# Nikon_PowerBoardV3.net
KiCad netlist of a schematic drawn in EAGLE
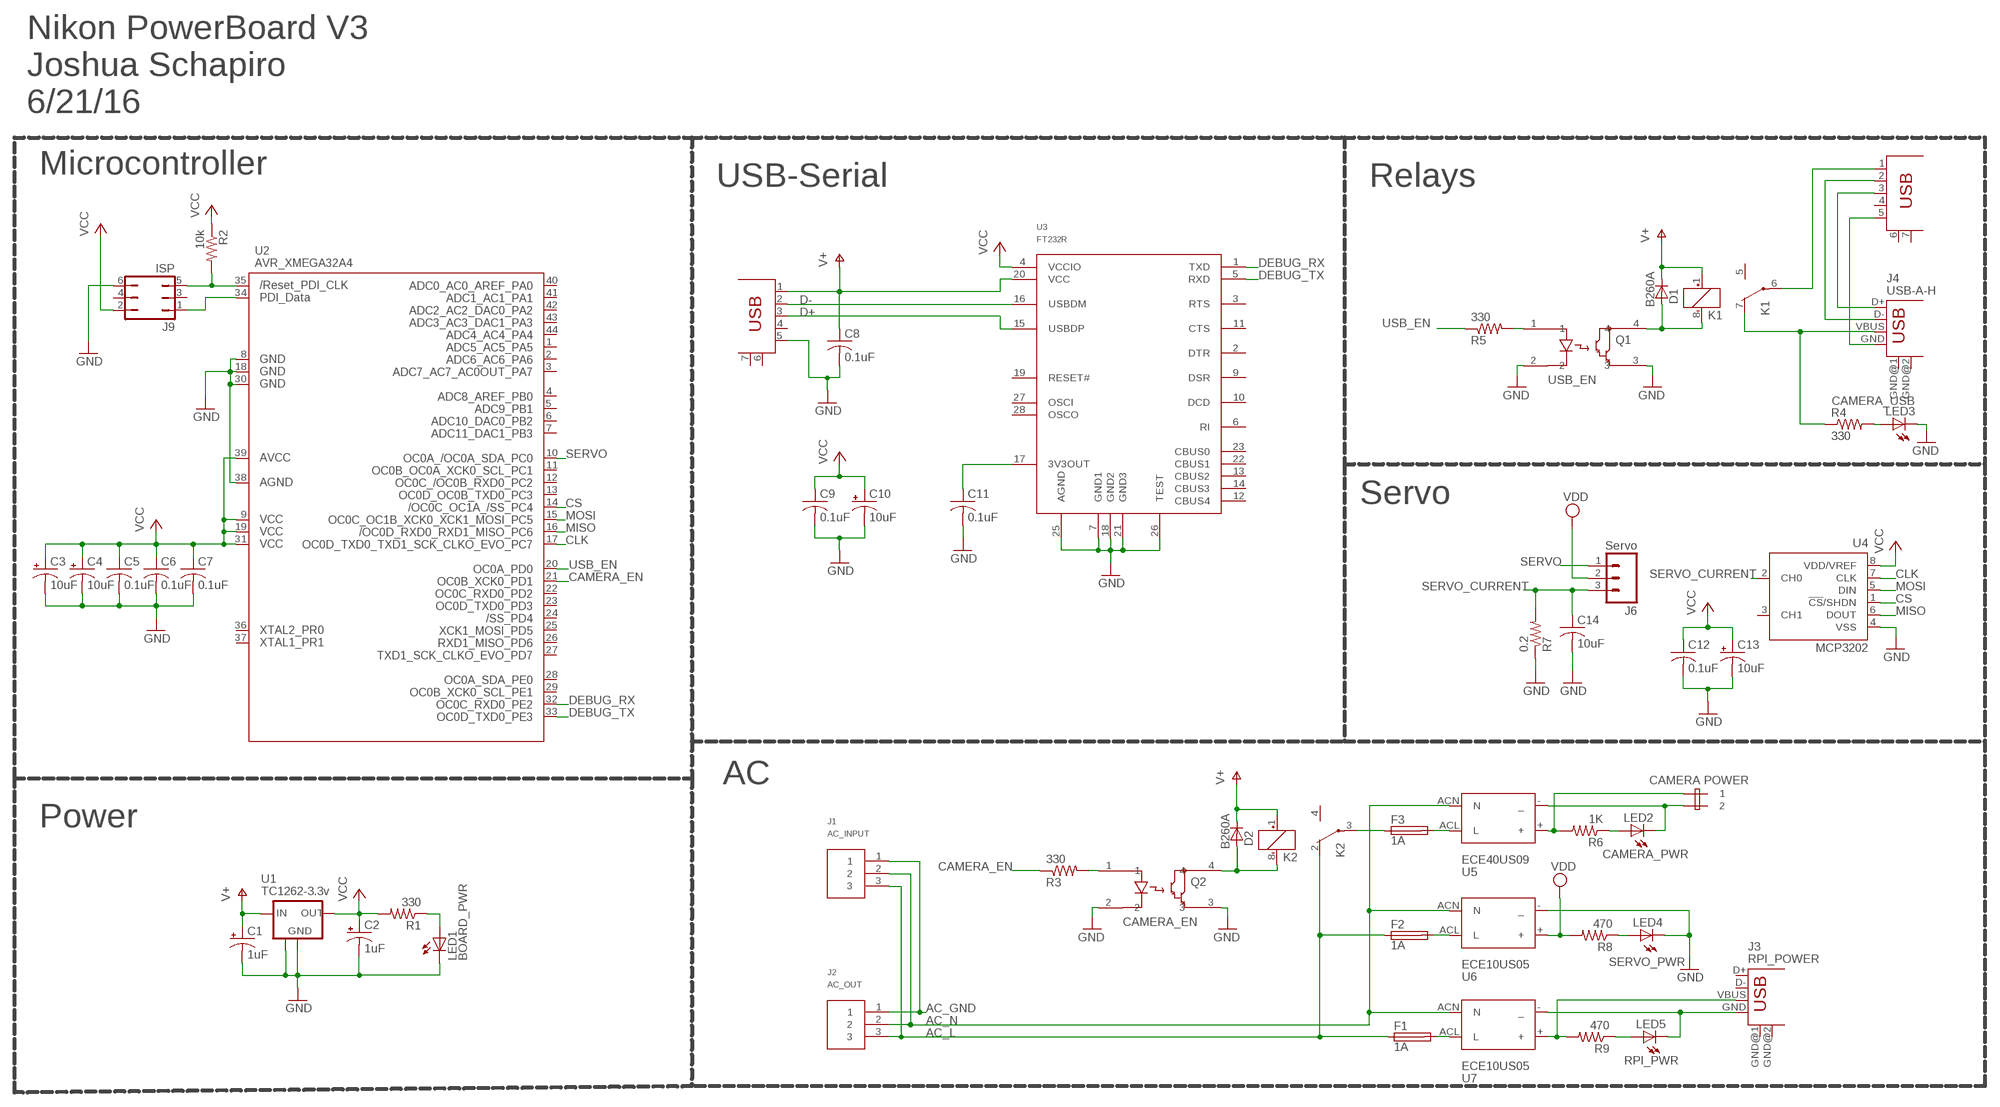
[diagram p0: schematic, sheet 1]

(export (version "E")
  (design (tool "Eeschema 10.0.6"))
  (components
    (comp (ref "C1")
      (value "1uF")
      (footprint "eagle-import:EIA3216")
      (libsource (lib "eagle-import") (part "CAP_POL1206"))
    )
    (comp (ref "C2")
      (value "1uF")
      (footprint "eagle-import:EIA3216")
      (libsource (lib "eagle-import") (part "CAP_POL1206"))
    )
    (comp (ref "C3")
      (value "10uF")
      (footprint "eagle-import:EIA3216")
      (libsource (lib "eagle-import") (part "CAP_POL1206"))
    )
    (comp (ref "C4")
      (value "10uF")
      (footprint "eagle-import:EIA3216")
      (libsource (lib "eagle-import") (part "CAP_POL1206"))
    )
    (comp (ref "C5")
      (value "0.1uF")
      (footprint "eagle-import:C0603")
      (libsource (lib "eagle-import") (part "C-USC0603"))
    )
    (comp (ref "C6")
      (value "0.1uF")
      (footprint "eagle-import:C0603")
      (libsource (lib "eagle-import") (part "resistor_C-USC0603"))
    )
    (comp (ref "C7")
      (value "0.1uF")
      (footprint "eagle-import:C0603")
      (libsource (lib "eagle-import") (part "resistor_C-USC0603"))
    )
    (comp (ref "C8")
      (value "0.1uF")
      (footprint "eagle-import:C0603")
      (libsource (lib "eagle-import") (part "resistor_C-USC0603"))
    )
    (comp (ref "C9")
      (value "0.1uF")
      (footprint "eagle-import:C0603")
      (libsource (lib "eagle-import") (part "resistor_C-USC0603"))
    )
    (comp (ref "C10")
      (value "10uF")
      (footprint "eagle-import:EIA3216")
      (libsource (lib "eagle-import") (part "CAP_POL1206"))
    )
    (comp (ref "C11")
      (value "0.1uF")
      (footprint "eagle-import:C0603")
      (libsource (lib "eagle-import") (part "resistor_C-USC0603"))
    )
    (comp (ref "C12")
      (value "0.1uF")
      (footprint "eagle-import:C0603")
      (libsource (lib "eagle-import") (part "resistor_C-USC0603"))
    )
    (comp (ref "C13")
      (value "10uF")
      (footprint "eagle-import:EIA3216")
      (libsource (lib "eagle-import") (part "CAP_POL1206"))
    )
    (comp (ref "C14")
      (value "10uF")
      (footprint "eagle-import:C1206")
      (libsource (lib "eagle-import") (part "resistor_C-USC1206"))
    )
    (comp (ref "D1")
      (value "B260A")
      (footprint "eagle-import:SMA-DIODE")
      (libsource (lib "eagle-import") (part "DIODESMA"))
    )
    (comp (ref "D2")
      (value "B260A")
      (footprint "eagle-import:SMA-DIODE")
      (libsource (lib "eagle-import") (part "DIODESMA"))
    )
    (comp (ref "F1")
      (value "1A")
      (footprint "eagle-import:19560")
      (libsource (lib "eagle-import") (part "19560"))
    )
    (comp (ref "F2")
      (value "1A")
      (footprint "eagle-import:19560")
      (libsource (lib "eagle-import") (part "19560"))
    )
    (comp (ref "F3")
      (value "1A")
      (footprint "eagle-import:19560")
      (libsource (lib "eagle-import") (part "19560"))
    )
    (comp (ref "J1")
      (value "AC_INPUT")
      (footprint "eagle-import:3-PIN-SCREW")
      (libsource (lib "eagle-import") (part "3-PIN-SCREW"))
    )
    (comp (ref "J2")
      (value "AC_OUT")
      (footprint "eagle-import:3-PIN-SCREW")
      (libsource (lib "eagle-import") (part "3-PIN-SCREW"))
    )
    (comp (ref "J3")
      (value "RPI_POWER")
      (footprint "eagle-import:USB-A-H")
      (libsource (lib "eagle-import") (part "USB-A-H"))
    )
    (comp (ref "J4")
      (value "USB-A-H")
      (footprint "eagle-import:USB-A-H")
      (libsource (lib "eagle-import") (part "USB-A-H"))
    )
    (comp (ref "J5")
      (value "CAMERA POWER")
      (footprint "eagle-import:2-PIN_SCREWTERM")
      (libsource (lib "eagle-import") (part "2-PIN_SCREWTERMINAL"))
    )
    (comp (ref "J6")
      (value "Servo")
      (footprint "eagle-import:1X03_LONGPADS")
      (libsource (lib "eagle-import") (part "M03LONGPADS"))
    )
    (comp (ref "J7")
      (value "MICRO-USB")
      (footprint "eagle-import:MICRO_USB_SM_W__TO_PINS")
      (libsource (lib "eagle-import") (part "MICRO-USBTO_SUPPORT"))
    )
    (comp (ref "J8")
      (value "MICRO-USB")
      (footprint "eagle-import:MICRO_USB_SM_W__TO_PINS")
      (libsource (lib "eagle-import") (part "MICRO-USBTO_SUPPORT"))
    )
    (comp (ref "J9")
      (value "ISP")
      (footprint "eagle-import:JP3Q")
      (libsource (lib "eagle-import") (part "JP3Q"))
    )
    (comp (ref "K1")
      (value "USB_EN")
      (footprint "eagle-import:G6K-2F")
      (libsource (lib "eagle-import") (part "G6K-2F"))
    )
    (comp (ref "K2")
      (value "CAMERA_EN")
      (footprint "eagle-import:G6K-2F")
      (libsource (lib "eagle-import") (part "G6K-2F"))
    )
    (comp (ref "LED1")
      (value "BOARD_PWR")
      (footprint "eagle-import:CHIPLED_0603")
      (libsource (lib "eagle-import") (part "LEDCHIPLED_0603"))
    )
    (comp (ref "LED2")
      (value "CAMERA_PWR")
      (footprint "eagle-import:CHIPLED_0603")
      (libsource (lib "eagle-import") (part "LEDCHIPLED_0603"))
    )
    (comp (ref "LED3")
      (value "CAMERA_USB")
      (footprint "eagle-import:CHIPLED_0603")
      (libsource (lib "eagle-import") (part "LEDCHIPLED_0603"))
    )
    (comp (ref "LED4")
      (value "SERVO_PWR")
      (footprint "eagle-import:CHIPLED_0603")
      (libsource (lib "eagle-import") (part "LEDCHIPLED_0603"))
    )
    (comp (ref "LED5")
      (value "RPI_PWR")
      (footprint "eagle-import:CHIPLED_0603")
      (libsource (lib "eagle-import") (part "LEDCHIPLED_0603"))
    )
    (comp (ref "Q1")
      (value "USB_EN")
      (footprint "eagle-import:4-PIN_MINI-FLAT")
      (libsource (lib "eagle-import") (part "OPTOISOLATOR_SINGLE"))
    )
    (comp (ref "Q2")
      (value "CAMERA_EN")
      (footprint "eagle-import:4-PIN_MINI-FLAT")
      (libsource (lib "eagle-import") (part "OPTOISOLATOR_SINGLE"))
    )
    (comp (ref "R1")
      (value "330")
      (footprint "eagle-import:R0603")
      (libsource (lib "eagle-import") (part "resistor_R-US_R0603"))
    )
    (comp (ref "R2")
      (value "10k")
      (footprint "eagle-import:R0603")
      (libsource (lib "eagle-import") (part "resistor_R-US_R0603"))
    )
    (comp (ref "R3")
      (value "330")
      (footprint "eagle-import:R0603")
      (libsource (lib "eagle-import") (part "resistor_R-US_R0603"))
    )
    (comp (ref "R4")
      (value "330")
      (footprint "eagle-import:R0603")
      (libsource (lib "eagle-import") (part "resistor_R-US_R0603"))
    )
    (comp (ref "R5")
      (value "330")
      (footprint "eagle-import:R0603")
      (libsource (lib "eagle-import") (part "resistor_R-US_R0603"))
    )
    (comp (ref "R6")
      (value "1K")
      (footprint "eagle-import:R0603")
      (libsource (lib "eagle-import") (part "resistor_R-US_R0603"))
    )
    (comp (ref "R7")
      (value "0.2")
      (footprint "eagle-import:R1206")
      (libsource (lib "eagle-import") (part "R-US_R1206"))
    )
    (comp (ref "R8")
      (value "470")
      (footprint "eagle-import:R0603")
      (libsource (lib "eagle-import") (part "resistor_R-US_R0603"))
    )
    (comp (ref "R9")
      (value "470")
      (footprint "eagle-import:R0603")
      (libsource (lib "eagle-import") (part "resistor_R-US_R0603"))
    )
    (comp (ref "U1")
      (value "TC1262-3.3v")
      (footprint "eagle-import:SOT223")
      (libsource (lib "eagle-import") (part "REGULATOR"))
    )
    (comp (ref "U2")
      (value "AVR_XMEGA32A4")
      (footprint "eagle-import:TQFP44")
      (libsource (lib "eagle-import") (part "AVR_XMEGA_A4_44A"))
    )
    (comp (ref "U3")
      (value "FT232R")
      (footprint "eagle-import:SSOP28")
      (libsource (lib "eagle-import") (part "FT232R"))
    )
    (comp (ref "U4")
      (value "MCP3202")
      (footprint "eagle-import:SO-08")
      (libsource (lib "eagle-import") (part "MCP3202SN"))
    )
    (comp (ref "U5")
      (value "ECE40US09")
      (footprint "eagle-import:EC40")
      (libsource (lib "eagle-import") (part "AC_DC_CONVERTERUS09"))
    )
    (comp (ref "U6")
      (value "ECE10US05")
      (footprint "eagle-import:ECE10")
      (libsource (lib "eagle-import") (part "AC_DC_CONVERTERUS05"))
    )
    (comp (ref "U7")
      (value "ECE10US05")
      (footprint "eagle-import:ECE10")
      (libsource (lib "eagle-import") (part "AC_DC_CONVERTERUS05"))
    )
  )
  (nets
    (net (code "1") (name "/AC_GND") (class "Default")
      (node (ref "J1") (pin "1") (pinfunction "1_1") (pintype "bidirectional"))
      (node (ref "J2") (pin "1") (pinfunction "1_1") (pintype "bidirectional"))
    )
    (net (code "2") (name "/AC_L") (class "Default")
      (node (ref "F1") (pin "1") (pinfunction "1_1") (pintype "passive"))
      (node (ref "F2") (pin "1") (pinfunction "1_1") (pintype "passive"))
      (node (ref "J1") (pin "3") (pinfunction "3_3") (pintype "bidirectional"))
      (node (ref "J2") (pin "3") (pinfunction "3_3") (pintype "bidirectional"))
      (node (ref "K2") (pin "2") (pinfunction "O_2") (pintype "passive"))
    )
    (net (code "3") (name "/AC_N") (class "Default")
      (node (ref "J1") (pin "2") (pinfunction "2_2") (pintype "bidirectional"))
      (node (ref "J2") (pin "2") (pinfunction "2_2") (pintype "bidirectional"))
      (node (ref "U5") (pin "ACN") (pinfunction "N_ACN") (pintype "bidirectional"))
      (node (ref "U6") (pin "ACN") (pinfunction "N_ACN") (pintype "bidirectional"))
      (node (ref "U7") (pin "ACN") (pinfunction "N_ACN") (pintype "bidirectional"))
    )
    (net (code "4") (name "/CAMERA_EN") (class "Default")
      (node (ref "R3") (pin "1") (pinfunction "1_1") (pintype "passive"))
      (node (ref "U2") (pin "21") (pinfunction "PD1_21") (pintype "bidirectional"))
    )
    (net (code "5") (name "/CLK") (class "Default")
      (node (ref "U2") (pin "17") (pinfunction "PC7_17") (pintype "bidirectional"))
      (node (ref "U4") (pin "7") (pinfunction "CLK_7") (pintype "input"))
    )
    (net (code "6") (name "/CS") (class "Default")
      (node (ref "U2") (pin "14") (pinfunction "PC4_14") (pintype "bidirectional"))
      (node (ref "U4") (pin "1") (pinfunction "~{CS}/SHDN_1") (pintype "input"))
    )
    (net (code "7") (name "/D+") (class "Default")
      (node (ref "J8") (pin "3") (pinfunction "D+_3") (pintype "bidirectional"))
      (node (ref "U3") (pin "15") (pinfunction "USBDP_15") (pintype "bidirectional"))
    )
    (net (code "8") (name "/D-") (class "Default")
      (node (ref "J8") (pin "2") (pinfunction "D-_2") (pintype "bidirectional"))
      (node (ref "U3") (pin "16") (pinfunction "USBDM_16") (pintype "bidirectional"))
    )
    (net (code "9") (name "/DEBUG_RX") (class "Default")
      (node (ref "U2") (pin "32") (pinfunction "PE2_32") (pintype "bidirectional"))
      (node (ref "U3") (pin "1") (pinfunction "TXD_1") (pintype "bidirectional"))
    )
    (net (code "10") (name "/DEBUG_TX") (class "Default")
      (node (ref "U2") (pin "33") (pinfunction "PE3_33") (pintype "bidirectional"))
      (node (ref "U3") (pin "5") (pinfunction "RXD_5") (pintype "bidirectional"))
    )
    (net (code "11") (name "/MISO") (class "Default")
      (node (ref "U2") (pin "16") (pinfunction "PC6_16") (pintype "bidirectional"))
      (node (ref "U4") (pin "6") (pinfunction "DOUT_6") (pintype "input"))
    )
    (net (code "12") (name "/MOSI") (class "Default")
      (node (ref "U2") (pin "15") (pinfunction "PC5_15") (pintype "bidirectional"))
      (node (ref "U4") (pin "5") (pinfunction "DIN_5") (pintype "input"))
    )
    (net (code "13") (name "/SERVO") (class "Default")
      (node (ref "J6") (pin "1") (pinfunction "1_1") (pintype "passive"))
      (node (ref "U2") (pin "10") (pinfunction "PC0_10") (pintype "bidirectional"))
    )
    (net (code "14") (name "/SERVO_CURRENT") (class "Default")
      (node (ref "C14") (pin "1") (pinfunction "1_1") (pintype "passive"))
      (node (ref "J6") (pin "3") (pinfunction "3_3") (pintype "passive"))
      (node (ref "R7") (pin "2") (pinfunction "2_2") (pintype "passive"))
      (node (ref "U4") (pin "2") (pinfunction "CH0_2") (pintype "input"))
    )
    (net (code "15") (name "/USB_EN") (class "Default")
      (node (ref "R5") (pin "1") (pinfunction "1_1") (pintype "passive"))
      (node (ref "U2") (pin "20") (pinfunction "PD0_20") (pintype "bidirectional"))
    )
    (net (code "16") (name "GND") (class "Default")
      (node (ref "C1") (pin "C") (pinfunction "-_C") (pintype "passive"))
      (node (ref "C10") (pin "C") (pinfunction "-_C") (pintype "passive"))
      (node (ref "C11") (pin "2") (pinfunction "2_2") (pintype "passive"))
      (node (ref "C12") (pin "2") (pinfunction "2_2") (pintype "passive"))
      (node (ref "C13") (pin "C") (pinfunction "-_C") (pintype "passive"))
      (node (ref "C14") (pin "2") (pinfunction "2_2") (pintype "passive"))
      (node (ref "C2") (pin "C") (pinfunction "-_C") (pintype "passive"))
      (node (ref "C3") (pin "C") (pinfunction "-_C") (pintype "passive"))
      (node (ref "C4") (pin "C") (pinfunction "-_C") (pintype "passive"))
      (node (ref "C5") (pin "2") (pinfunction "2_2") (pintype "passive"))
      (node (ref "C6") (pin "2") (pinfunction "2_2") (pintype "passive"))
      (node (ref "C7") (pin "2") (pinfunction "2_2") (pintype "passive"))
      (node (ref "C8") (pin "2") (pinfunction "2_2") (pintype "passive"))
      (node (ref "C9") (pin "2") (pinfunction "2_2") (pintype "passive"))
      (node (ref "J8") (pin "5") (pinfunction "GND_5") (pintype "bidirectional"))
      (node (ref "J9") (pin "6") (pinfunction "6_6") (pintype "passive"))
      (node (ref "LED1") (pin "C") (pinfunction "C_C") (pintype "passive"))
      (node (ref "LED3") (pin "C") (pinfunction "C_C") (pintype "passive"))
      (node (ref "LED4") (pin "C") (pinfunction "C_C") (pintype "passive"))
      (node (ref "Q1") (pin "2") (pinfunction "2_2") (pintype "bidirectional"))
      (node (ref "Q1") (pin "3") (pinfunction "3_3") (pintype "bidirectional"))
      (node (ref "Q2") (pin "2") (pinfunction "2_2") (pintype "bidirectional"))
      (node (ref "Q2") (pin "3") (pinfunction "3_3") (pintype "bidirectional"))
      (node (ref "R7") (pin "1") (pinfunction "1_1") (pintype "passive"))
      (node (ref "U1") (pin "2") (pinfunction "GND_2") (pintype "bidirectional"))
      (node (ref "U1") (pin "4") (pinfunction "GND1_4") (pintype "bidirectional"))
      (node (ref "U2") (pin "18") (pinfunction "GND2_18") (pintype "bidirectional"))
      (node (ref "U2") (pin "30") (pinfunction "GND3_30") (pintype "bidirectional"))
      (node (ref "U2") (pin "38") (pinfunction "AGND_38") (pintype "bidirectional"))
      (node (ref "U2") (pin "8") (pinfunction "GND1_8") (pintype "bidirectional"))
      (node (ref "U3") (pin "18") (pinfunction "GND2_18") (pintype "bidirectional"))
      (node (ref "U3") (pin "21") (pinfunction "GND3_21") (pintype "bidirectional"))
      (node (ref "U3") (pin "25") (pinfunction "AGND_25") (pintype "bidirectional"))
      (node (ref "U3") (pin "26") (pinfunction "TEST_26") (pintype "bidirectional"))
      (node (ref "U3") (pin "7") (pinfunction "GND1_7") (pintype "bidirectional"))
      (node (ref "U4") (pin "4") (pinfunction "VSS_4") (pintype "input"))
      (node (ref "U6") (pin "-") (pinfunction "__-") (pintype "bidirectional"))
    )
    (net (code "17") (name "Net-(J3-PadVBUS)") (class "Default")
      (node (ref "J3") (pin "VBUS") (pinfunction "VBUS_VBUS") (pintype "bidirectional"))
      (node (ref "R9") (pin "2") (pinfunction "2_2") (pintype "passive"))
      (node (ref "U7") (pin "+") (pinfunction "+_+") (pintype "bidirectional"))
    )
    (net (code "18") (name "Net-(J5-1)") (class "Default")
      (node (ref "J5") (pin "P$1") (pinfunction "1_P$1") (pintype "bidirectional"))
      (node (ref "R6") (pin "2") (pinfunction "2_2") (pintype "passive"))
      (node (ref "U5") (pin "+") (pinfunction "+_+") (pintype "bidirectional"))
    )
    (net (code "19") (name "Net-(J5-2)") (class "Default")
      (node (ref "J5") (pin "P$2") (pinfunction "2_P$2") (pintype "bidirectional"))
      (node (ref "LED2") (pin "C") (pinfunction "C_C") (pintype "passive"))
      (node (ref "U5") (pin "-") (pinfunction "__-") (pintype "bidirectional"))
    )
    (net (code "20") (name "Net-(J7-D+)") (class "Default")
      (node (ref "J4") (pin "D+") (pinfunction "D+_D+") (pintype "bidirectional"))
      (node (ref "J7") (pin "3") (pinfunction "D+_3") (pintype "bidirectional"))
    )
    (net (code "21") (name "Net-(J7-D-)") (class "Default")
      (node (ref "J4") (pin "D-") (pinfunction "D-_D-") (pintype "bidirectional"))
      (node (ref "J7") (pin "2") (pinfunction "D-_2") (pintype "bidirectional"))
    )
    (net (code "22") (name "Net-(J7-GND)") (class "Default")
      (node (ref "J4") (pin "GND") (pinfunction "GND_GND") (pintype "bidirectional"))
      (node (ref "J7") (pin "5") (pinfunction "GND_5") (pintype "bidirectional"))
    )
    (net (code "23") (name "Net-(J7-VBUS)") (class "Default")
      (node (ref "J7") (pin "1") (pinfunction "VBUS_1") (pintype "bidirectional"))
      (node (ref "K1") (pin "6") (pinfunction "P_6") (pintype "passive"))
    )
    (net (code "24") (name "Net-(K1A--)") (class "Default")
      (node (ref "D1") (pin "A") (pinfunction "A_A") (pintype "passive"))
      (node (ref "K1") (pin "8") (pinfunction "-_8") (pintype "passive"))
      (node (ref "Q1") (pin "4") (pinfunction "4_4") (pintype "bidirectional"))
    )
    (net (code "25") (name "Net-(K1C-O)") (class "Default")
      (node (ref "J4") (pin "VBUS") (pinfunction "VBUS_VBUS") (pintype "bidirectional"))
      (node (ref "K1") (pin "7") (pinfunction "O_7") (pintype "passive"))
      (node (ref "R4") (pin "1") (pinfunction "1_1") (pintype "passive"))
    )
    (net (code "26") (name "Net-(K2A--)") (class "Default")
      (node (ref "D2") (pin "A") (pinfunction "A_A") (pintype "passive"))
      (node (ref "K2") (pin "8") (pinfunction "-_8") (pintype "passive"))
      (node (ref "Q2") (pin "4") (pinfunction "4_4") (pintype "bidirectional"))
    )
    (net (code "27") (name "Net-(K2B-P)") (class "Default")
      (node (ref "F3") (pin "1") (pinfunction "1_1") (pintype "passive"))
      (node (ref "K2") (pin "3") (pinfunction "P_3") (pintype "passive"))
    )
    (net (code "28") (name "Net-(LED1-PadA)") (class "Default")
      (node (ref "LED1") (pin "A") (pinfunction "A_A") (pintype "passive"))
      (node (ref "R1") (pin "1") (pinfunction "1_1") (pintype "passive"))
    )
    (net (code "29") (name "Net-(LED2-PadA)") (class "Default")
      (node (ref "LED2") (pin "A") (pinfunction "A_A") (pintype "passive"))
      (node (ref "R6") (pin "1") (pinfunction "1_1") (pintype "passive"))
    )
    (net (code "30") (name "Net-(LED3-PadA)") (class "Default")
      (node (ref "LED3") (pin "A") (pinfunction "A_A") (pintype "passive"))
      (node (ref "R4") (pin "2") (pinfunction "2_2") (pintype "passive"))
    )
    (net (code "31") (name "Net-(LED4-PadA)") (class "Default")
      (node (ref "LED4") (pin "A") (pinfunction "A_A") (pintype "passive"))
      (node (ref "R8") (pin "1") (pinfunction "1_1") (pintype "passive"))
    )
    (net (code "32") (name "Net-(LED5-PadA)") (class "Default")
      (node (ref "LED5") (pin "A") (pinfunction "A_A") (pintype "passive"))
      (node (ref "R9") (pin "1") (pinfunction "1_1") (pintype "passive"))
    )
    (net (code "33") (name "Net-(Q1-Pad1)") (class "Default")
      (node (ref "Q1") (pin "1") (pinfunction "1_1") (pintype "bidirectional"))
      (node (ref "R5") (pin "2") (pinfunction "2_2") (pintype "passive"))
    )
    (net (code "34") (name "Net-(Q2-Pad1)") (class "Default")
      (node (ref "Q2") (pin "1") (pinfunction "1_1") (pintype "bidirectional"))
      (node (ref "R3") (pin "2") (pinfunction "2_2") (pintype "passive"))
    )
    (net (code "35") (name "Net-(U2-PDI_DATA)") (class "Default")
      (node (ref "J9") (pin "1") (pinfunction "1_1") (pintype "passive"))
      (node (ref "U2") (pin "34") (pinfunction "PDI_DATA_34") (pintype "bidirectional"))
    )
    (net (code "36") (name "Net-(U2-RESET)") (class "Default")
      (node (ref "J9") (pin "5") (pinfunction "5_5") (pintype "passive"))
      (node (ref "R2") (pin "2") (pinfunction "2_2") (pintype "passive"))
      (node (ref "U2") (pin "35") (pinfunction "RESET_35") (pintype "bidirectional"))
    )
    (net (code "37") (name "Net-(U3-3V3OUT)") (class "Default")
      (node (ref "C11") (pin "1") (pinfunction "1_1") (pintype "passive"))
      (node (ref "U3") (pin "17") (pinfunction "3V3OUT_17") (pintype "bidirectional"))
    )
    (net (code "38") (name "Net-(U5-L)") (class "Default")
      (node (ref "F3") (pin "2") (pinfunction "2_2") (pintype "passive"))
      (node (ref "U5") (pin "ACL") (pinfunction "L_ACL") (pintype "bidirectional"))
    )
    (net (code "39") (name "Net-(U6-L)") (class "Default")
      (node (ref "F2") (pin "2") (pinfunction "2_2") (pintype "passive"))
      (node (ref "U6") (pin "ACL") (pinfunction "L_ACL") (pintype "bidirectional"))
    )
    (net (code "40") (name "Net-(U7-L)") (class "Default")
      (node (ref "F1") (pin "2") (pinfunction "2_2") (pintype "passive"))
      (node (ref "U7") (pin "ACL") (pinfunction "L_ACL") (pintype "bidirectional"))
    )
    (net (code "41") (name "Net-(U7-_)") (class "Default")
      (node (ref "J3") (pin "GND") (pinfunction "GND_GND") (pintype "bidirectional"))
      (node (ref "LED5") (pin "C") (pinfunction "C_C") (pintype "passive"))
      (node (ref "U7") (pin "-") (pinfunction "__-") (pintype "bidirectional"))
    )
    (net (code "42") (name "V+") (class "Default")
      (node (ref "C1") (pin "A") (pinfunction "+_A") (pintype "passive"))
      (node (ref "C8") (pin "1") (pinfunction "1_1") (pintype "passive"))
      (node (ref "D1") (pin "C") (pinfunction "C_C") (pintype "passive"))
      (node (ref "D2") (pin "C") (pinfunction "C_C") (pintype "passive"))
      (node (ref "J8") (pin "1") (pinfunction "VBUS_1") (pintype "bidirectional"))
      (node (ref "K1") (pin "1") (pinfunction "+_1") (pintype "passive"))
      (node (ref "K2") (pin "1") (pinfunction "+_1") (pintype "passive"))
      (node (ref "U1") (pin "1") (pinfunction "IN_1") (pintype "bidirectional"))
      (node (ref "U3") (pin "20") (pinfunction "VCC_20") (pintype "bidirectional"))
    )
    (net (code "43") (name "VCC") (class "Default")
      (node (ref "C10") (pin "A") (pinfunction "+_A") (pintype "passive"))
      (node (ref "C12") (pin "1") (pinfunction "1_1") (pintype "passive"))
      (node (ref "C13") (pin "A") (pinfunction "+_A") (pintype "passive"))
      (node (ref "C2") (pin "A") (pinfunction "+_A") (pintype "passive"))
      (node (ref "C3") (pin "A") (pinfunction "+_A") (pintype "passive"))
      (node (ref "C4") (pin "A") (pinfunction "+_A") (pintype "passive"))
      (node (ref "C5") (pin "1") (pinfunction "1_1") (pintype "passive"))
      (node (ref "C6") (pin "1") (pinfunction "1_1") (pintype "passive"))
      (node (ref "C7") (pin "1") (pinfunction "1_1") (pintype "passive"))
      (node (ref "C9") (pin "1") (pinfunction "1_1") (pintype "passive"))
      (node (ref "J9") (pin "2") (pinfunction "2_2") (pintype "passive"))
      (node (ref "R1") (pin "2") (pinfunction "2_2") (pintype "passive"))
      (node (ref "R2") (pin "1") (pinfunction "1_1") (pintype "passive"))
      (node (ref "U1") (pin "3") (pinfunction "OUT_3") (pintype "bidirectional"))
      (node (ref "U2") (pin "19") (pinfunction "VCC2_19") (pintype "bidirectional"))
      (node (ref "U2") (pin "31") (pinfunction "VCC3_31") (pintype "bidirectional"))
      (node (ref "U2") (pin "39") (pinfunction "AVCC_39") (pintype "bidirectional"))
      (node (ref "U2") (pin "9") (pinfunction "VCC1_9") (pintype "bidirectional"))
      (node (ref "U3") (pin "4") (pinfunction "VCCIO_4") (pintype "bidirectional"))
      (node (ref "U4") (pin "8") (pinfunction "VDD/VREF_8") (pintype "input"))
    )
    (net (code "44") (name "VDD") (class "Default")
      (node (ref "J6") (pin "2") (pinfunction "2_2") (pintype "passive"))
      (node (ref "R8") (pin "2") (pinfunction "2_2") (pintype "passive"))
      (node (ref "U6") (pin "+") (pinfunction "+_+") (pintype "bidirectional"))
    )
    (net (code "45") (name "unconnected-(J3-GND-PadGND@1)") (class "Default")
      (node (ref "J3") (pin "GND@1") (pinfunction "GND_GND@1") (pintype "bidirectional"))
    )
    (net (code "46") (name "unconnected-(J3-GND-PadGND@2)") (class "Default")
      (node (ref "J3") (pin "GND@2") (pinfunction "GND_GND@2") (pintype "bidirectional"))
    )
    (net (code "47") (name "unconnected-(J3-PadD+)") (class "Default")
      (node (ref "J3") (pin "D+") (pinfunction "D+_D+") (pintype "bidirectional"))
    )
    (net (code "48") (name "unconnected-(J3-PadD-)") (class "Default")
      (node (ref "J3") (pin "D-") (pinfunction "D-_D-") (pintype "bidirectional"))
    )
    (net (code "49") (name "unconnected-(J4-GND-PadGND@1)") (class "Default")
      (node (ref "J4") (pin "GND@1") (pinfunction "GND_GND@1") (pintype "bidirectional"))
    )
    (net (code "50") (name "unconnected-(J4-GND-PadGND@2)") (class "Default")
      (node (ref "J4") (pin "GND@2") (pinfunction "GND_GND@2") (pintype "bidirectional"))
    )
    (net (code "51") (name "unconnected-(J7-ID-Pad4)") (class "Default")
      (node (ref "J7") (pin "4") (pinfunction "ID_4") (pintype "bidirectional"))
    )
    (net (code "52") (name "unconnected-(J7-MTN3-Pad6)") (class "Default")
      (node (ref "J7") (pin "6") (pinfunction "MTN3_6") (pintype "bidirectional"))
    )
    (net (code "53") (name "unconnected-(J7-MTN4-Pad7)") (class "Default")
      (node (ref "J7") (pin "7") (pinfunction "MTN4_7") (pintype "bidirectional"))
    )
    (net (code "54") (name "unconnected-(J8-ID-Pad4)") (class "Default")
      (node (ref "J8") (pin "4") (pinfunction "ID_4") (pintype "bidirectional"))
    )
    (net (code "55") (name "unconnected-(J8-MTN3-Pad6)") (class "Default")
      (node (ref "J8") (pin "6") (pinfunction "MTN3_6") (pintype "bidirectional"))
    )
    (net (code "56") (name "unconnected-(J8-MTN4-Pad7)") (class "Default")
      (node (ref "J8") (pin "7") (pinfunction "MTN4_7") (pintype "bidirectional"))
    )
    (net (code "57") (name "unconnected-(J9-Pad3)") (class "Default")
      (node (ref "J9") (pin "3") (pinfunction "3_3") (pintype "passive"))
    )
    (net (code "58") (name "unconnected-(J9-Pad4)") (class "Default")
      (node (ref "J9") (pin "4") (pinfunction "4_4") (pintype "passive"))
    )
    (net (code "59") (name "unconnected-(K1C-S-Pad5)") (class "Default")
      (node (ref "K1") (pin "5") (pinfunction "S_5") (pintype "passive"))
    )
    (net (code "60") (name "unconnected-(K2B-S-Pad4)") (class "Default")
      (node (ref "K2") (pin "4") (pinfunction "S_4") (pintype "passive"))
    )
    (net (code "61") (name "unconnected-(U2-PA0-Pad40)") (class "Default")
      (node (ref "U2") (pin "40") (pinfunction "PA0_40") (pintype "bidirectional"))
    )
    (net (code "62") (name "unconnected-(U2-PA1-Pad41)") (class "Default")
      (node (ref "U2") (pin "41") (pinfunction "PA1_41") (pintype "bidirectional"))
    )
    (net (code "63") (name "unconnected-(U2-PA2-Pad42)") (class "Default")
      (node (ref "U2") (pin "42") (pinfunction "PA2_42") (pintype "bidirectional"))
    )
    (net (code "64") (name "unconnected-(U2-PA3-Pad43)") (class "Default")
      (node (ref "U2") (pin "43") (pinfunction "PA3_43") (pintype "bidirectional"))
    )
    (net (code "65") (name "unconnected-(U2-PA4-Pad44)") (class "Default")
      (node (ref "U2") (pin "44") (pinfunction "PA4_44") (pintype "bidirectional"))
    )
    (net (code "66") (name "unconnected-(U2-PA5-Pad1)") (class "Default")
      (node (ref "U2") (pin "1") (pinfunction "PA5_1") (pintype "bidirectional"))
    )
    (net (code "67") (name "unconnected-(U2-PA6-Pad2)") (class "Default")
      (node (ref "U2") (pin "2") (pinfunction "PA6_2") (pintype "bidirectional"))
    )
    (net (code "68") (name "unconnected-(U2-PA7-Pad3)") (class "Default")
      (node (ref "U2") (pin "3") (pinfunction "PA7_3") (pintype "bidirectional"))
    )
    (net (code "69") (name "unconnected-(U2-PB0-Pad4)") (class "Default")
      (node (ref "U2") (pin "4") (pinfunction "PB0_4") (pintype "bidirectional"))
    )
    (net (code "70") (name "unconnected-(U2-PB1-Pad5)") (class "Default")
      (node (ref "U2") (pin "5") (pinfunction "PB1_5") (pintype "bidirectional"))
    )
    (net (code "71") (name "unconnected-(U2-PB2-Pad6)") (class "Default")
      (node (ref "U2") (pin "6") (pinfunction "PB2_6") (pintype "bidirectional"))
    )
    (net (code "72") (name "unconnected-(U2-PB3-Pad7)") (class "Default")
      (node (ref "U2") (pin "7") (pinfunction "PB3_7") (pintype "bidirectional"))
    )
    (net (code "73") (name "unconnected-(U2-PC1-Pad11)") (class "Default")
      (node (ref "U2") (pin "11") (pinfunction "PC1_11") (pintype "bidirectional"))
    )
    (net (code "74") (name "unconnected-(U2-PC2-Pad12)") (class "Default")
      (node (ref "U2") (pin "12") (pinfunction "PC2_12") (pintype "bidirectional"))
    )
    (net (code "75") (name "unconnected-(U2-PC3-Pad13)") (class "Default")
      (node (ref "U2") (pin "13") (pinfunction "PC3_13") (pintype "bidirectional"))
    )
    (net (code "76") (name "unconnected-(U2-PD2-Pad22)") (class "Default")
      (node (ref "U2") (pin "22") (pinfunction "PD2_22") (pintype "bidirectional"))
    )
    (net (code "77") (name "unconnected-(U2-PD3-Pad23)") (class "Default")
      (node (ref "U2") (pin "23") (pinfunction "PD3_23") (pintype "bidirectional"))
    )
    (net (code "78") (name "unconnected-(U2-PD4-Pad24)") (class "Default")
      (node (ref "U2") (pin "24") (pinfunction "PD4_24") (pintype "bidirectional"))
    )
    (net (code "79") (name "unconnected-(U2-PD5-Pad25)") (class "Default")
      (node (ref "U2") (pin "25") (pinfunction "PD5_25") (pintype "bidirectional"))
    )
    (net (code "80") (name "unconnected-(U2-PD6-Pad26)") (class "Default")
      (node (ref "U2") (pin "26") (pinfunction "PD6_26") (pintype "bidirectional"))
    )
    (net (code "81") (name "unconnected-(U2-PD7-Pad27)") (class "Default")
      (node (ref "U2") (pin "27") (pinfunction "PD7_27") (pintype "bidirectional"))
    )
    (net (code "82") (name "unconnected-(U2-PE0-Pad28)") (class "Default")
      (node (ref "U2") (pin "28") (pinfunction "PE0_28") (pintype "bidirectional"))
    )
    (net (code "83") (name "unconnected-(U2-PE1-Pad29)") (class "Default")
      (node (ref "U2") (pin "29") (pinfunction "PE1_29") (pintype "bidirectional"))
    )
    (net (code "84") (name "unconnected-(U2-PR0-Pad36)") (class "Default")
      (node (ref "U2") (pin "36") (pinfunction "PR0_36") (pintype "bidirectional"))
    )
    (net (code "85") (name "unconnected-(U2-PR1-Pad37)") (class "Default")
      (node (ref "U2") (pin "37") (pinfunction "PR1_37") (pintype "bidirectional"))
    )
    (net (code "86") (name "unconnected-(U3-CBUS0-Pad23)") (class "Default")
      (node (ref "U3") (pin "23") (pinfunction "CBUS0_23") (pintype "bidirectional"))
    )
    (net (code "87") (name "unconnected-(U3-CBUS1-Pad22)") (class "Default")
      (node (ref "U3") (pin "22") (pinfunction "CBUS1_22") (pintype "bidirectional"))
    )
    (net (code "88") (name "unconnected-(U3-CBUS2-Pad13)") (class "Default")
      (node (ref "U3") (pin "13") (pinfunction "CBUS2_13") (pintype "bidirectional"))
    )
    (net (code "89") (name "unconnected-(U3-CBUS3-Pad14)") (class "Default")
      (node (ref "U3") (pin "14") (pinfunction "CBUS3_14") (pintype "bidirectional"))
    )
    (net (code "90") (name "unconnected-(U3-CBUS4-Pad12)") (class "Default")
      (node (ref "U3") (pin "12") (pinfunction "CBUS4_12") (pintype "bidirectional"))
    )
    (net (code "91") (name "unconnected-(U3-CTS-Pad11)") (class "Default")
      (node (ref "U3") (pin "11") (pinfunction "CTS_11") (pintype "bidirectional"))
    )
    (net (code "92") (name "unconnected-(U3-DCD-Pad10)") (class "Default")
      (node (ref "U3") (pin "10") (pinfunction "DCD_10") (pintype "bidirectional"))
    )
    (net (code "93") (name "unconnected-(U3-DSR-Pad9)") (class "Default")
      (node (ref "U3") (pin "9") (pinfunction "DSR_9") (pintype "bidirectional"))
    )
    (net (code "94") (name "unconnected-(U3-DTR-Pad2)") (class "Default")
      (node (ref "U3") (pin "2") (pinfunction "DTR_2") (pintype "bidirectional"))
    )
    (net (code "95") (name "unconnected-(U3-OSCI-Pad27)") (class "Default")
      (node (ref "U3") (pin "27") (pinfunction "OSCI_27") (pintype "bidirectional"))
    )
    (net (code "96") (name "unconnected-(U3-OSCO-Pad28)") (class "Default")
      (node (ref "U3") (pin "28") (pinfunction "OSCO_28") (pintype "bidirectional"))
    )
    (net (code "97") (name "unconnected-(U3-RESET#-Pad19)") (class "Default")
      (node (ref "U3") (pin "19") (pinfunction "RESET#_19") (pintype "bidirectional"))
    )
    (net (code "98") (name "unconnected-(U3-RI-Pad6)") (class "Default")
      (node (ref "U3") (pin "6") (pinfunction "RI_6") (pintype "bidirectional"))
    )
    (net (code "99") (name "unconnected-(U3-RTS-Pad3)") (class "Default")
      (node (ref "U3") (pin "3") (pinfunction "RTS_3") (pintype "bidirectional"))
    )
    (net (code "100") (name "unconnected-(U4-CH1-Pad3)") (class "Default")
      (node (ref "U4") (pin "3") (pinfunction "CH1_3") (pintype "input"))
    )
  )
)
